# main.net
KiCad netlist of a schematic drawn in EAGLE
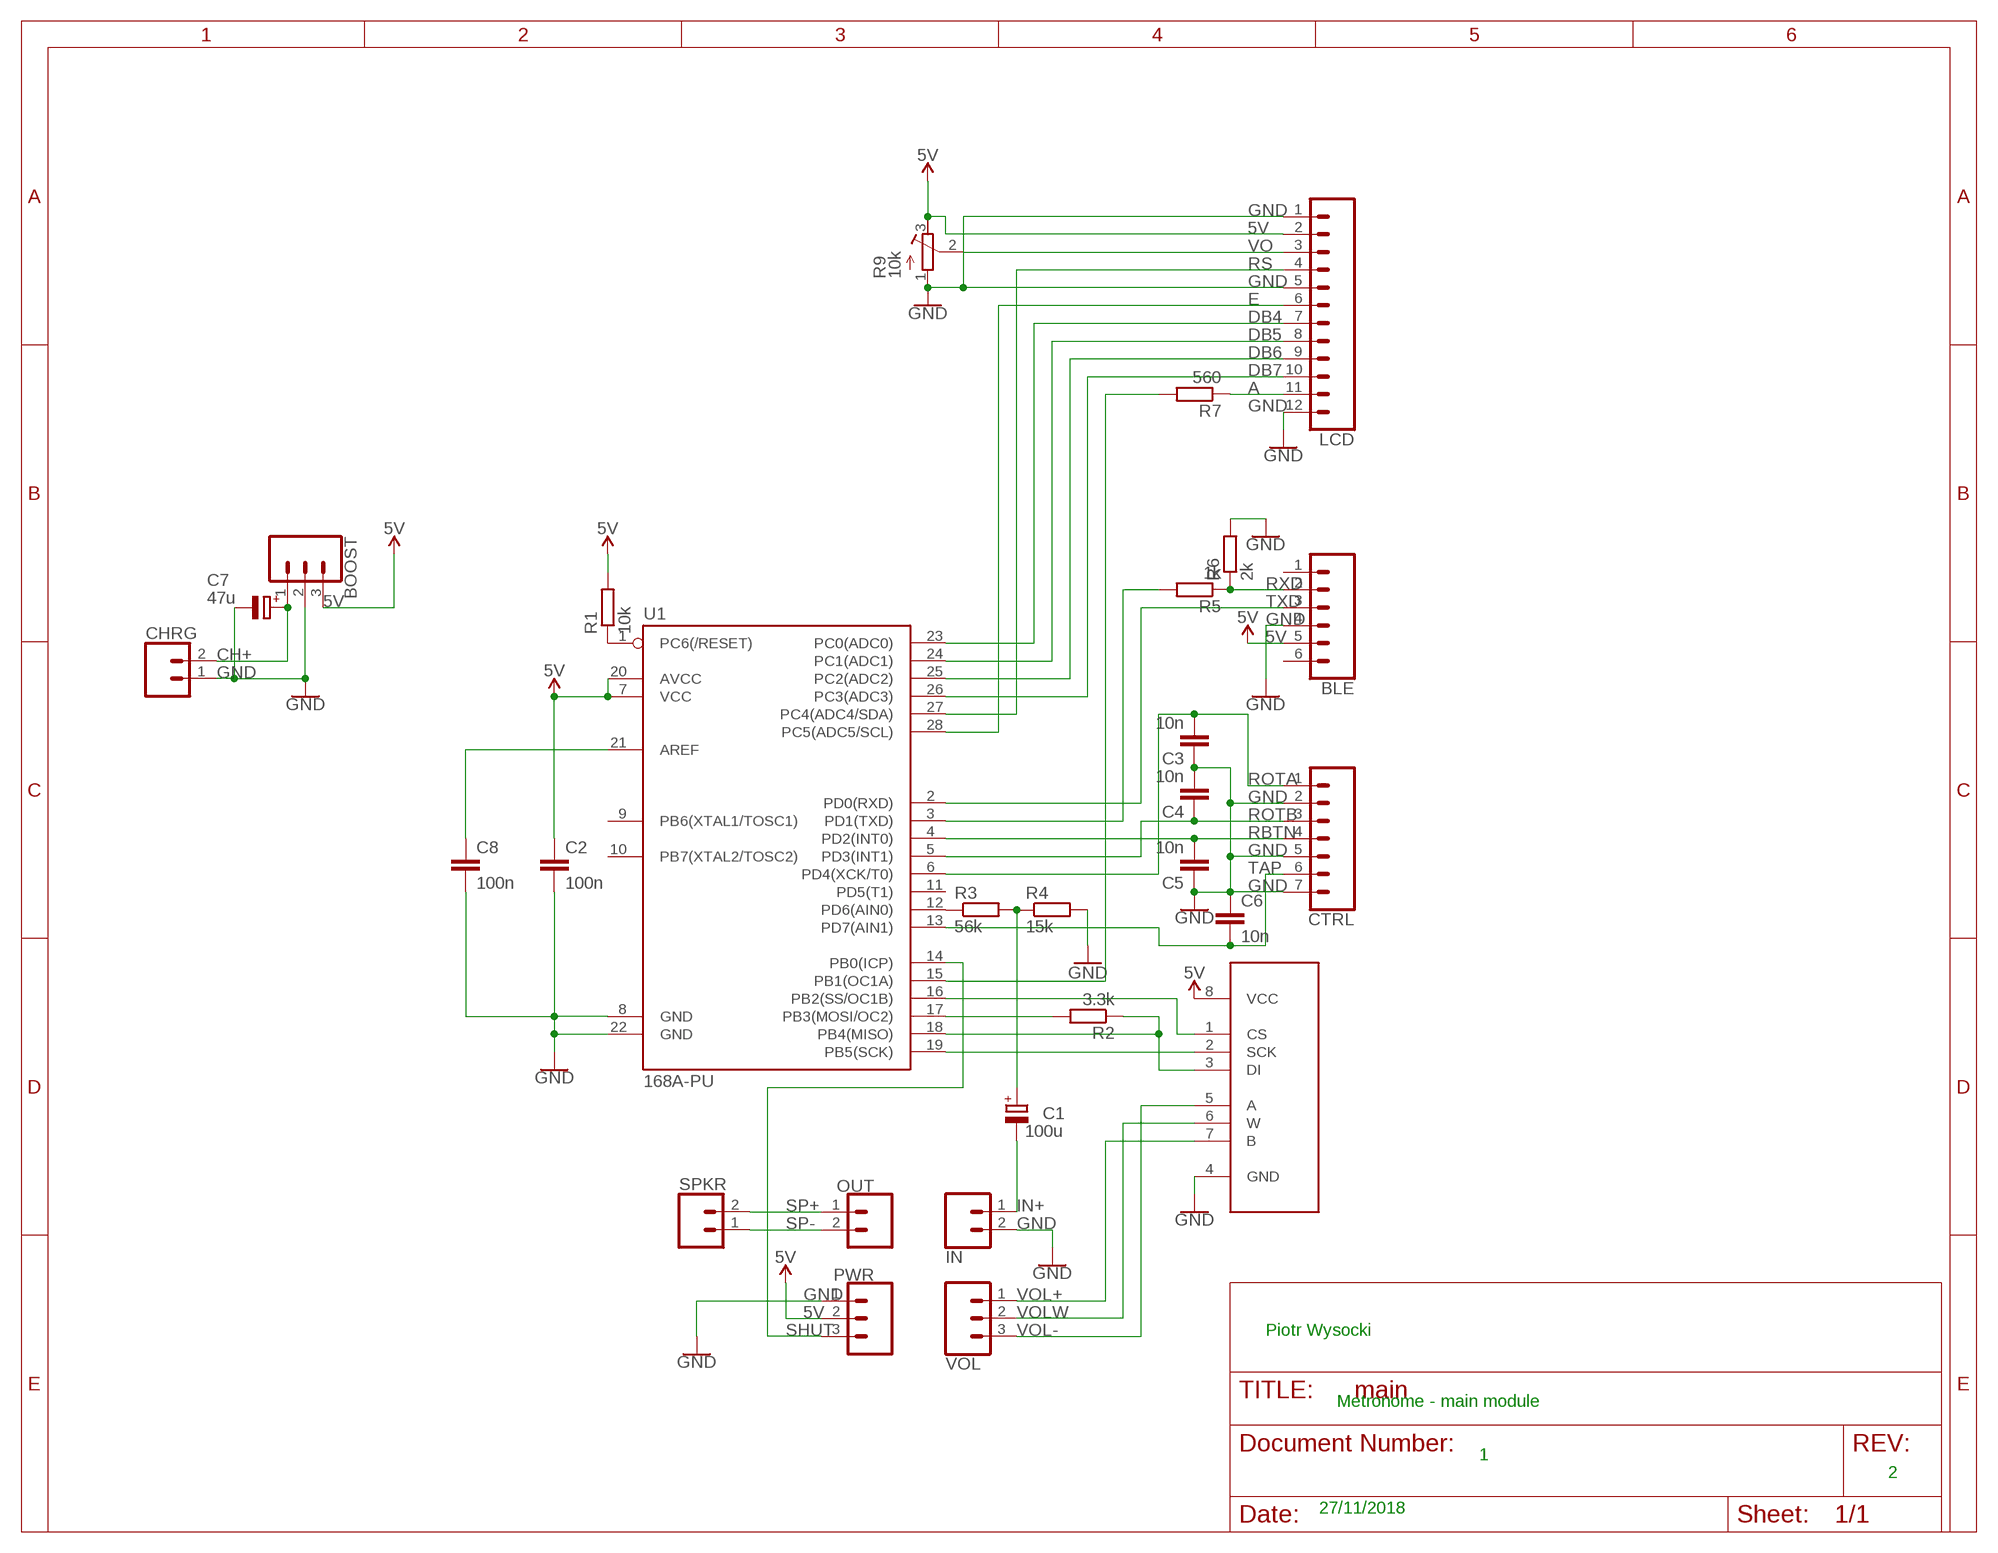
[diagram p0: schematic, sheet 1]

(export (version "E")
  (design (tool "Eeschema 10.0.6"))
  (components
    (comp (ref "BLE")
      (value "CONN_06SILK_FEMALE_PTH")
      (footprint "eagle-import:1X06")
      (libsource (lib "eagle-import") (part "CONN_06SILK_FEMALE_PTH"))
    )
    (comp (ref "BOOST")
      (value "CONN_03")
      (footprint "eagle-import:1X03")
      (libsource (lib "eagle-import") (part "CONN_03"))
    )
    (comp (ref "C1")
      (value "100u")
      (footprint "eagle-import:E3,5-8")
      (libsource (lib "eagle-import") (part "CPOL-EUE3.5-8"))
    )
    (comp (ref "C2")
      (value "100n")
      (footprint "eagle-import:C025-024X044")
      (libsource (lib "eagle-import") (part "C-EU025-024X044"))
    )
    (comp (ref "C3")
      (value "10n")
      (footprint "eagle-import:C025-024X044")
      (libsource (lib "eagle-import") (part "C-EU025-024X044"))
    )
    (comp (ref "C4")
      (value "10n")
      (footprint "eagle-import:C025-024X044")
      (libsource (lib "eagle-import") (part "C-EU025-024X044"))
    )
    (comp (ref "C5")
      (value "10n")
      (footprint "eagle-import:C025-024X044")
      (libsource (lib "eagle-import") (part "C-EU025-024X044"))
    )
    (comp (ref "C6")
      (value "10n")
      (footprint "eagle-import:C025-024X044")
      (libsource (lib "eagle-import") (part "C-EU025-024X044"))
    )
    (comp (ref "C7")
      (value "47u")
      (footprint "eagle-import:E2,5-7")
      (libsource (lib "eagle-import") (part "CPOL-EUE2.5-7"))
    )
    (comp (ref "C8")
      (value "100n")
      (footprint "eagle-import:C025-024X044")
      (libsource (lib "eagle-import") (part "C-EU025-024X044"))
    )
    (comp (ref "CHRG")
      (value "CONN_02")
      (footprint "eagle-import:1X02")
      (libsource (lib "eagle-import") (part "CONN_02"))
    )
    (comp (ref "CTRL")
      (value "CONN_07")
      (footprint "eagle-import:1X07")
      (libsource (lib "eagle-import") (part "CONN_07"))
    )
    (comp (ref "IN")
      (value "CONN_02")
      (footprint "eagle-import:1X02")
      (libsource (lib "eagle-import") (part "CONN_02"))
    )
    (comp (ref "LCD")
      (value "CONN_12")
      (footprint "eagle-import:1X12")
      (libsource (lib "eagle-import") (part "CONN_12"))
    )
    (comp (ref "MCP4161")
      (value "MCP41XXX")
      (footprint "eagle-import:DIP08")
      (libsource (lib "eagle-import") (part "MCP41XXXDIL"))
    )
    (comp (ref "OUT")
      (value "CONN_02")
      (footprint "eagle-import:1X02")
      (libsource (lib "eagle-import") (part "CONN_02"))
    )
    (comp (ref "PWR")
      (value "CONN_03")
      (footprint "eagle-import:1X03")
      (libsource (lib "eagle-import") (part "CONN_03"))
    )
    (comp (ref "R1")
      (value "10k")
      (footprint "eagle-import:0204_7")
      (libsource (lib "eagle-import") (part "R-EU_0204/7"))
    )
    (comp (ref "R2")
      (value "3.3k")
      (footprint "eagle-import:0204_7")
      (libsource (lib "eagle-import") (part "R-EU_0204/7"))
    )
    (comp (ref "R3")
      (value "56k")
      (footprint "eagle-import:0204_7")
      (libsource (lib "eagle-import") (part "R-EU_0204/7"))
    )
    (comp (ref "R4")
      (value "15k")
      (footprint "eagle-import:0204_7")
      (libsource (lib "eagle-import") (part "R-EU_0204/7"))
    )
    (comp (ref "R5")
      (value "1k")
      (footprint "eagle-import:0204_7")
      (libsource (lib "eagle-import") (part "R-EU_0204/7"))
    )
    (comp (ref "R6")
      (value "2k")
      (footprint "eagle-import:0204_7")
      (libsource (lib "eagle-import") (part "R-EU_0204/7"))
    )
    (comp (ref "R7")
      (value "560")
      (footprint "eagle-import:0204_7")
      (libsource (lib "eagle-import") (part "R-EU_0204/7"))
    )
    (comp (ref "R9")
      (value "10k")
      (footprint "eagle-import:RTRIM3296W")
      (libsource (lib "eagle-import") (part "R-TRIMM3296W"))
    )
    (comp (ref "SPKR")
      (value "CONN_02")
      (footprint "eagle-import:1X02")
      (libsource (lib "eagle-import") (part "CONN_02"))
    )
    (comp (ref "U1")
      (value "168A-PU")
      (footprint "eagle-import:DIP28")
      (libsource (lib "eagle-import") (part "ATMEGA328P_PDIP"))
    )
    (comp (ref "VOL")
      (value "CONN_03")
      (footprint "eagle-import:1X03")
      (libsource (lib "eagle-import") (part "CONN_03"))
    )
  )
  (nets
    (net (code "1") (name "/A") (class "Default")
      (node (ref "LCD") (pin "11") (pinfunction "11_11") (pintype "passive"))
      (node (ref "R7") (pin "1") (pinfunction "1_1") (pintype "passive"))
    )
    (net (code "2") (name "/CH+") (class "Default")
      (node (ref "BOOST") (pin "1") (pinfunction "1_1") (pintype "passive"))
      (node (ref "C7") (pin "+") (pinfunction "+_+") (pintype "passive"))
      (node (ref "CHRG") (pin "2") (pinfunction "2_2") (pintype "passive"))
    )
    (net (code "3") (name "/DB4") (class "Default")
      (node (ref "LCD") (pin "7") (pinfunction "7_7") (pintype "passive"))
      (node (ref "U1") (pin "23") (pinfunction "PC0(ADC0)_23") (pintype "bidirectional"))
    )
    (net (code "4") (name "/DB5") (class "Default")
      (node (ref "LCD") (pin "8") (pinfunction "8_8") (pintype "passive"))
      (node (ref "U1") (pin "24") (pinfunction "PC1(ADC1)_24") (pintype "bidirectional"))
    )
    (net (code "5") (name "/DB6") (class "Default")
      (node (ref "LCD") (pin "9") (pinfunction "9_9") (pintype "passive"))
      (node (ref "U1") (pin "25") (pinfunction "PC2(ADC2)_25") (pintype "bidirectional"))
    )
    (net (code "6") (name "/DB7") (class "Default")
      (node (ref "LCD") (pin "10") (pinfunction "10_10") (pintype "passive"))
      (node (ref "U1") (pin "26") (pinfunction "PC3(ADC3)_26") (pintype "bidirectional"))
    )
    (net (code "7") (name "/E") (class "Default")
      (node (ref "LCD") (pin "6") (pinfunction "6_6") (pintype "passive"))
      (node (ref "U1") (pin "28") (pinfunction "PC5(ADC5/SCL)_28") (pintype "bidirectional"))
    )
    (net (code "8") (name "/IN+") (class "Default")
      (node (ref "C1") (pin "-") (pinfunction "-_-") (pintype "passive"))
      (node (ref "IN") (pin "1") (pinfunction "1_1") (pintype "passive"))
    )
    (net (code "9") (name "/RBTN") (class "Default")
      (node (ref "C5") (pin "2") (pinfunction "2_2") (pintype "passive"))
      (node (ref "CTRL") (pin "4") (pinfunction "4_4") (pintype "passive"))
      (node (ref "U1") (pin "4") (pinfunction "PD2(INT0)_4") (pintype "bidirectional"))
    )
    (net (code "10") (name "/ROTA") (class "Default")
      (node (ref "C3") (pin "2") (pinfunction "2_2") (pintype "passive"))
      (node (ref "CTRL") (pin "1") (pinfunction "1_1") (pintype "passive"))
      (node (ref "U1") (pin "6") (pinfunction "PD4(XCK/T0)_6") (pintype "bidirectional"))
    )
    (net (code "11") (name "/ROTB") (class "Default")
      (node (ref "C4") (pin "1") (pinfunction "1_1") (pintype "passive"))
      (node (ref "CTRL") (pin "3") (pinfunction "3_3") (pintype "passive"))
      (node (ref "U1") (pin "5") (pinfunction "PD3(INT1)_5") (pintype "bidirectional"))
    )
    (net (code "12") (name "/RS") (class "Default")
      (node (ref "LCD") (pin "4") (pinfunction "4_4") (pintype "passive"))
      (node (ref "U1") (pin "27") (pinfunction "PC4(ADC4/SDA)_27") (pintype "bidirectional"))
    )
    (net (code "13") (name "/RXD") (class "Default")
      (node (ref "BLE") (pin "2") (pinfunction "2_2") (pintype "passive"))
      (node (ref "R5") (pin "1") (pinfunction "1_1") (pintype "passive"))
      (node (ref "R6") (pin "1") (pinfunction "1_1") (pintype "passive"))
    )
    (net (code "14") (name "/SHUT") (class "Default")
      (node (ref "PWR") (pin "3") (pinfunction "3_3") (pintype "passive"))
      (node (ref "U1") (pin "14") (pinfunction "PB0(ICP)_14") (pintype "bidirectional"))
    )
    (net (code "15") (name "/SP+") (class "Default")
      (node (ref "OUT") (pin "1") (pinfunction "1_1") (pintype "passive"))
      (node (ref "SPKR") (pin "2") (pinfunction "2_2") (pintype "passive"))
    )
    (net (code "16") (name "/SP-") (class "Default")
      (node (ref "OUT") (pin "2") (pinfunction "2_2") (pintype "passive"))
      (node (ref "SPKR") (pin "1") (pinfunction "1_1") (pintype "passive"))
    )
    (net (code "17") (name "/TAP") (class "Default")
      (node (ref "C6") (pin "2") (pinfunction "2_2") (pintype "passive"))
      (node (ref "CTRL") (pin "6") (pinfunction "6_6") (pintype "passive"))
      (node (ref "U1") (pin "13") (pinfunction "PD7(AIN1)_13") (pintype "bidirectional"))
    )
    (net (code "18") (name "/TXD") (class "Default")
      (node (ref "BLE") (pin "3") (pinfunction "3_3") (pintype "passive"))
      (node (ref "U1") (pin "2") (pinfunction "PD0(RXD)_2") (pintype "bidirectional"))
    )
    (net (code "19") (name "/VO") (class "Default")
      (node (ref "LCD") (pin "3") (pinfunction "3_3") (pintype "passive"))
      (node (ref "R9") (pin "2") (pinfunction "S_2") (pintype "passive"))
    )
    (net (code "20") (name "/VOL+") (class "Default")
      (node (ref "MCP4161") (pin "7") (pinfunction "B_7") (pintype "bidirectional"))
      (node (ref "VOL") (pin "1") (pinfunction "1_1") (pintype "passive"))
    )
    (net (code "21") (name "/VOL-") (class "Default")
      (node (ref "MCP4161") (pin "5") (pinfunction "A_5") (pintype "bidirectional"))
      (node (ref "VOL") (pin "3") (pinfunction "3_3") (pintype "passive"))
    )
    (net (code "22") (name "/VOLW") (class "Default")
      (node (ref "MCP4161") (pin "6") (pinfunction "W_6") (pintype "bidirectional"))
      (node (ref "VOL") (pin "2") (pinfunction "2_2") (pintype "passive"))
    )
    (net (code "23") (name "5V") (class "Default")
      (node (ref "BLE") (pin "5") (pinfunction "5_5") (pintype "passive"))
      (node (ref "BOOST") (pin "3") (pinfunction "3_3") (pintype "passive"))
      (node (ref "C2") (pin "1") (pinfunction "1_1") (pintype "passive"))
      (node (ref "LCD") (pin "2") (pinfunction "2_2") (pintype "passive"))
      (node (ref "MCP4161") (pin "8") (pinfunction "VCC_8") (pintype "bidirectional"))
      (node (ref "PWR") (pin "2") (pinfunction "2_2") (pintype "passive"))
      (node (ref "R1") (pin "2") (pinfunction "2_2") (pintype "passive"))
      (node (ref "R9") (pin "3") (pinfunction "E_3") (pintype "passive"))
      (node (ref "U1") (pin "20") (pinfunction "AVCC_20") (pintype "bidirectional"))
      (node (ref "U1") (pin "7") (pinfunction "VCC_7") (pintype "bidirectional"))
    )
    (net (code "24") (name "GND") (class "Default")
      (node (ref "BLE") (pin "4") (pinfunction "4_4") (pintype "passive"))
      (node (ref "BOOST") (pin "2") (pinfunction "2_2") (pintype "passive"))
      (node (ref "C2") (pin "2") (pinfunction "2_2") (pintype "passive"))
      (node (ref "C3") (pin "1") (pinfunction "1_1") (pintype "passive"))
      (node (ref "C4") (pin "2") (pinfunction "2_2") (pintype "passive"))
      (node (ref "C5") (pin "1") (pinfunction "1_1") (pintype "passive"))
      (node (ref "C6") (pin "1") (pinfunction "1_1") (pintype "passive"))
      (node (ref "C7") (pin "-") (pinfunction "-_-") (pintype "passive"))
      (node (ref "C8") (pin "2") (pinfunction "2_2") (pintype "passive"))
      (node (ref "CHRG") (pin "1") (pinfunction "1_1") (pintype "passive"))
      (node (ref "CTRL") (pin "2") (pinfunction "2_2") (pintype "passive"))
      (node (ref "CTRL") (pin "5") (pinfunction "5_5") (pintype "passive"))
      (node (ref "CTRL") (pin "7") (pinfunction "7_7") (pintype "passive"))
      (node (ref "IN") (pin "2") (pinfunction "2_2") (pintype "passive"))
      (node (ref "LCD") (pin "1") (pinfunction "1_1") (pintype "passive"))
      (node (ref "LCD") (pin "12") (pinfunction "12_12") (pintype "passive"))
      (node (ref "LCD") (pin "5") (pinfunction "5_5") (pintype "passive"))
      (node (ref "MCP4161") (pin "4") (pinfunction "GND_4") (pintype "bidirectional"))
      (node (ref "PWR") (pin "1") (pinfunction "1_1") (pintype "passive"))
      (node (ref "R4") (pin "2") (pinfunction "2_2") (pintype "passive"))
      (node (ref "R6") (pin "2") (pinfunction "2_2") (pintype "passive"))
      (node (ref "R9") (pin "1") (pinfunction "A_1") (pintype "passive"))
      (node (ref "U1") (pin "22") (pinfunction "GND_22") (pintype "bidirectional"))
      (node (ref "U1") (pin "8") (pinfunction "GND_8") (pintype "bidirectional"))
    )
    (net (code "25") (name "Net-(C1-Pad+)") (class "Default")
      (node (ref "C1") (pin "+") (pinfunction "+_+") (pintype "passive"))
      (node (ref "R3") (pin "2") (pinfunction "2_2") (pintype "passive"))
      (node (ref "R4") (pin "1") (pinfunction "1_1") (pintype "passive"))
    )
    (net (code "26") (name "Net-(MCP4161-CS)") (class "Default")
      (node (ref "MCP4161") (pin "1") (pinfunction "CS_1") (pintype "bidirectional"))
      (node (ref "U1") (pin "16") (pinfunction "PB2(SS/OC1B)_16") (pintype "bidirectional"))
    )
    (net (code "27") (name "Net-(MCP4161-DI)") (class "Default")
      (node (ref "MCP4161") (pin "3") (pinfunction "DI_3") (pintype "bidirectional"))
      (node (ref "R2") (pin "1") (pinfunction "1_1") (pintype "passive"))
      (node (ref "U1") (pin "18") (pinfunction "PB4(MISO)_18") (pintype "bidirectional"))
    )
    (net (code "28") (name "Net-(MCP4161-SCK)") (class "Default")
      (node (ref "MCP4161") (pin "2") (pinfunction "SCK_2") (pintype "bidirectional"))
      (node (ref "U1") (pin "19") (pinfunction "PB5(SCK)_19") (pintype "bidirectional"))
    )
    (net (code "29") (name "Net-(U1-AREF)") (class "Default")
      (node (ref "C8") (pin "1") (pinfunction "1_1") (pintype "passive"))
      (node (ref "U1") (pin "21") (pinfunction "AREF_21") (pintype "bidirectional"))
    )
    (net (code "30") (name "Net-(U1-PB1(OC1A))") (class "Default")
      (node (ref "R7") (pin "2") (pinfunction "2_2") (pintype "passive"))
      (node (ref "U1") (pin "15") (pinfunction "PB1(OC1A)_15") (pintype "bidirectional"))
    )
    (net (code "31") (name "Net-(U1-PB3(MOSI{slash}OC2))") (class "Default")
      (node (ref "R2") (pin "2") (pinfunction "2_2") (pintype "passive"))
      (node (ref "U1") (pin "17") (pinfunction "PB3(MOSI/OC2)_17") (pintype "bidirectional"))
    )
    (net (code "32") (name "Net-(U1-PC6({slash}RESET))") (class "Default")
      (node (ref "R1") (pin "1") (pinfunction "1_1") (pintype "passive"))
      (node (ref "U1") (pin "1") (pinfunction "PC6(/RESET)_1") (pintype "bidirectional"))
    )
    (net (code "33") (name "Net-(U1-PD1(TXD))") (class "Default")
      (node (ref "R5") (pin "2") (pinfunction "2_2") (pintype "passive"))
      (node (ref "U1") (pin "3") (pinfunction "PD1(TXD)_3") (pintype "bidirectional"))
    )
    (net (code "34") (name "Net-(U1-PD6(AIN0))") (class "Default")
      (node (ref "R3") (pin "1") (pinfunction "1_1") (pintype "passive"))
      (node (ref "U1") (pin "12") (pinfunction "PD6(AIN0)_12") (pintype "bidirectional"))
    )
    (net (code "35") (name "unconnected-(BLE-Pad1)") (class "Default")
      (node (ref "BLE") (pin "1") (pinfunction "1_1") (pintype "passive"))
    )
    (net (code "36") (name "unconnected-(BLE-Pad6)") (class "Default")
      (node (ref "BLE") (pin "6") (pinfunction "6_6") (pintype "passive"))
    )
    (net (code "37") (name "unconnected-(U1-PB6(XTAL1{slash}TOSC1)-Pad9)") (class "Default")
      (node (ref "U1") (pin "9") (pinfunction "PB6(XTAL1/TOSC1)_9") (pintype "bidirectional"))
    )
    (net (code "38") (name "unconnected-(U1-PB7(XTAL2{slash}TOSC2)-Pad10)") (class "Default")
      (node (ref "U1") (pin "10") (pinfunction "PB7(XTAL2/TOSC2)_10") (pintype "bidirectional"))
    )
    (net (code "39") (name "unconnected-(U1-PD5(T1)-Pad11)") (class "Default")
      (node (ref "U1") (pin "11") (pinfunction "PD5(T1)_11") (pintype "bidirectional"))
    )
  )
)
